# tda.net
KiCad netlist of a schematic drawn in EAGLE
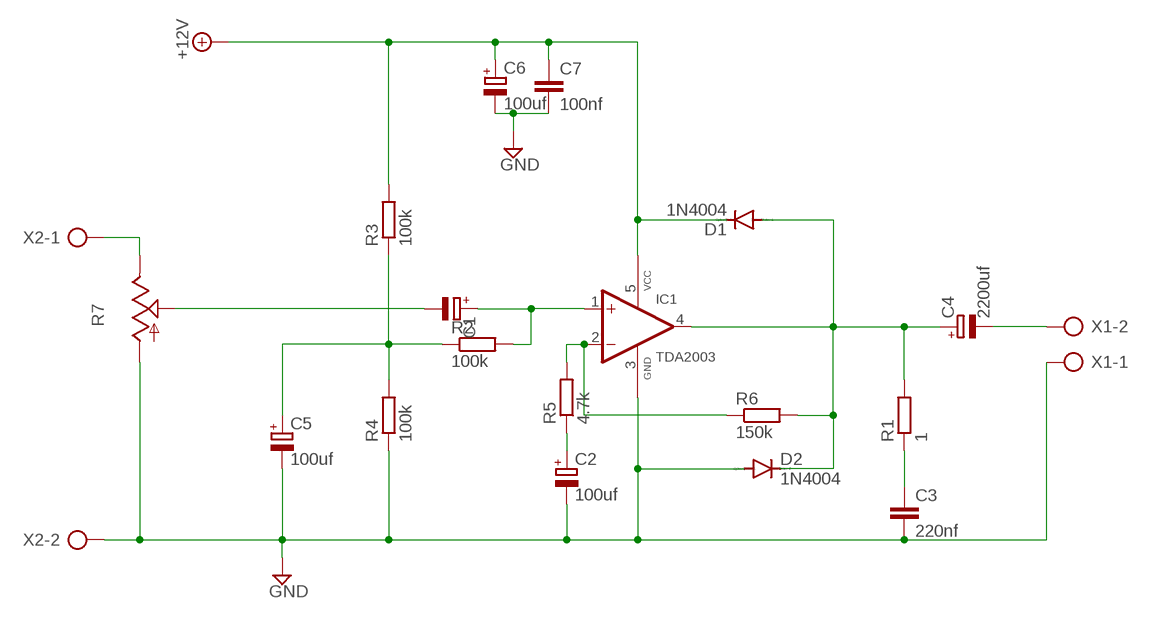
[diagram p0: schematic, sheet 1]

(export (version "E")
  (design (tool "Eeschema 10.0.6"))
  (components
    (comp (ref "C1")
      (value "CPOL-EUE2-5")
      (footprint "eagle-import:E2-5")
      (libsource (lib "eagle-import") (part "CPOL-EUE2-5"))
    )
    (comp (ref "C2")
      (value "100uf")
      (footprint "eagle-import:E2-5")
      (libsource (lib "eagle-import") (part "CPOL-EUE2-5"))
    )
    (comp (ref "C3")
      (value "220nf")
      (footprint "eagle-import:C025-030X050")
      (libsource (lib "eagle-import") (part "C-EU025-030X050"))
    )
    (comp (ref "C4")
      (value "2200uf")
      (footprint "eagle-import:E2-5")
      (libsource (lib "eagle-import") (part "CPOL-EUE2-5"))
    )
    (comp (ref "C5")
      (value "100uf")
      (footprint "eagle-import:E2-5")
      (libsource (lib "eagle-import") (part "CPOL-EUE2-5"))
    )
    (comp (ref "C6")
      (value "100uf")
      (footprint "eagle-import:E2-5")
      (libsource (lib "eagle-import") (part "CPOL-EUE2-5"))
    )
    (comp (ref "C7")
      (value "100nf")
      (footprint "eagle-import:C025-030X050")
      (libsource (lib "eagle-import") (part "C-EU025-030X050"))
    )
    (comp (ref "D1")
      (value "1N4004")
      (footprint "eagle-import:DO41-10")
      (libsource (lib "eagle-import") (part "1N4004"))
    )
    (comp (ref "D2")
      (value "1N4004")
      (footprint "eagle-import:DO41-10")
      (libsource (lib "eagle-import") (part "1N4004"))
    )
    (comp (ref "IC1")
      (value "TDA2003")
      (footprint "eagle-import:PENTAWATT-V")
      (libsource (lib "eagle-import") (part "TDA2003"))
    )
    (comp (ref "R1")
      (value "1")
      (footprint "eagle-import:0309_12")
      (libsource (lib "eagle-import") (part "R-EU_0309/12"))
    )
    (comp (ref "R2")
      (value "100k")
      (footprint "eagle-import:0309_12")
      (libsource (lib "eagle-import") (part "R-EU_0309/12"))
    )
    (comp (ref "R3")
      (value "100k")
      (footprint "eagle-import:0309_12")
      (libsource (lib "eagle-import") (part "R-EU_0309/12"))
    )
    (comp (ref "R4")
      (value "100k")
      (footprint "eagle-import:0309_12")
      (libsource (lib "eagle-import") (part "R-EU_0309/12"))
    )
    (comp (ref "R5")
      (value "4.7k")
      (footprint "eagle-import:0309_12")
      (libsource (lib "eagle-import") (part "R-EU_0309/12"))
    )
    (comp (ref "R6")
      (value "150k")
      (footprint "eagle-import:0309_12")
      (libsource (lib "eagle-import") (part "R-EU_0309/12"))
    )
    (comp (ref "R7")
      (value "TRIM_US-CIP20C-6MM")
      (footprint "eagle-import:CIP20C-6MM")
      (libsource (lib "eagle-import") (part "TRIM_US-CIP20C-6MM"))
    )
    (comp (ref "X1")
      (value "AK300/2")
      (footprint "eagle-import:AK300_2")
      (libsource (lib "eagle-import") (part "AK300/2"))
    )
    (comp (ref "X2")
      (value "AK300/2")
      (footprint "eagle-import:AK300_2")
      (libsource (lib "eagle-import") (part "AK300/2"))
    )
  )
  (nets
    (net (code "1") (name "+12V") (class "Default")
      (node (ref "C6") (pin "+") (pinfunction "+_+") (pintype "passive"))
      (node (ref "C7") (pin "1") (pinfunction "1_1") (pintype "passive"))
      (node (ref "D1") (pin "C") (pinfunction "C_C") (pintype "passive"))
      (node (ref "IC1") (pin "5") (pinfunction "VCC_5") (pintype "power_in"))
      (node (ref "R3") (pin "2") (pinfunction "2_2") (pintype "passive"))
    )
    (net (code "2") (name "GND") (class "Default")
      (node (ref "C2") (pin "-") (pinfunction "-_-") (pintype "passive"))
      (node (ref "C3") (pin "2") (pinfunction "2_2") (pintype "passive"))
      (node (ref "C5") (pin "-") (pinfunction "-_-") (pintype "passive"))
      (node (ref "C6") (pin "-") (pinfunction "-_-") (pintype "passive"))
      (node (ref "C7") (pin "2") (pinfunction "2_2") (pintype "passive"))
      (node (ref "D2") (pin "A") (pinfunction "A_A") (pintype "passive"))
      (node (ref "IC1") (pin "3") (pinfunction "GND_3") (pintype "power_in"))
      (node (ref "R4") (pin "1") (pinfunction "1_1") (pintype "passive"))
      (node (ref "R7") (pin "A") (pinfunction "A_A") (pintype "passive"))
      (node (ref "X1") (pin "1") (pinfunction "KL_1") (pintype "passive"))
      (node (ref "X2") (pin "2") (pinfunction "KL_2") (pintype "passive"))
    )
    (net (code "3") (name "Net-(C1-Pad-)") (class "Default")
      (node (ref "C1") (pin "-") (pinfunction "-_-") (pintype "passive"))
      (node (ref "R7") (pin "S") (pinfunction "S_S") (pintype "passive"))
    )
    (net (code "4") (name "Net-(C2-Pad+)") (class "Default")
      (node (ref "C2") (pin "+") (pinfunction "+_+") (pintype "passive"))
      (node (ref "R5") (pin "1") (pinfunction "1_1") (pintype "passive"))
    )
    (net (code "5") (name "Net-(C3-Pad1)") (class "Default")
      (node (ref "C3") (pin "1") (pinfunction "1_1") (pintype "passive"))
      (node (ref "R1") (pin "1") (pinfunction "1_1") (pintype "passive"))
    )
    (net (code "6") (name "Net-(C5-Pad+)") (class "Default")
      (node (ref "C5") (pin "+") (pinfunction "+_+") (pintype "passive"))
      (node (ref "R2") (pin "1") (pinfunction "1_1") (pintype "passive"))
      (node (ref "R3") (pin "1") (pinfunction "1_1") (pintype "passive"))
      (node (ref "R4") (pin "2") (pinfunction "2_2") (pintype "passive"))
    )
    (net (code "7") (name "Net-(IC1-+IN)") (class "Default")
      (node (ref "C1") (pin "+") (pinfunction "+_+") (pintype "passive"))
      (node (ref "IC1") (pin "1") (pinfunction "+IN_1") (pintype "input"))
      (node (ref "R2") (pin "2") (pinfunction "2_2") (pintype "passive"))
    )
    (net (code "8") (name "Net-(IC1--IN)") (class "Default")
      (node (ref "IC1") (pin "2") (pinfunction "-IN_2") (pintype "input"))
      (node (ref "R5") (pin "2") (pinfunction "2_2") (pintype "passive"))
      (node (ref "R6") (pin "1") (pinfunction "1_1") (pintype "passive"))
    )
    (net (code "9") (name "Net-(IC1-OUT)") (class "Default")
      (node (ref "C4") (pin "+") (pinfunction "+_+") (pintype "passive"))
      (node (ref "D1") (pin "A") (pinfunction "A_A") (pintype "passive"))
      (node (ref "D2") (pin "C") (pinfunction "C_C") (pintype "passive"))
      (node (ref "IC1") (pin "4") (pinfunction "OUT_4") (pintype "output"))
      (node (ref "R1") (pin "2") (pinfunction "2_2") (pintype "passive"))
      (node (ref "R6") (pin "2") (pinfunction "2_2") (pintype "passive"))
    )
    (net (code "10") (name "Net-(X1B-KL)") (class "Default")
      (node (ref "C4") (pin "-") (pinfunction "-_-") (pintype "passive"))
      (node (ref "X1") (pin "2") (pinfunction "KL_2") (pintype "passive"))
    )
    (net (code "11") (name "Net-(X2A-KL)") (class "Default")
      (node (ref "R7") (pin "E") (pinfunction "E_E") (pintype "passive"))
      (node (ref "X2") (pin "1") (pinfunction "KL_1") (pintype "passive"))
    )
  )
)
